# Inverter.net
KiCad netlist of a schematic drawn in Altium Designer
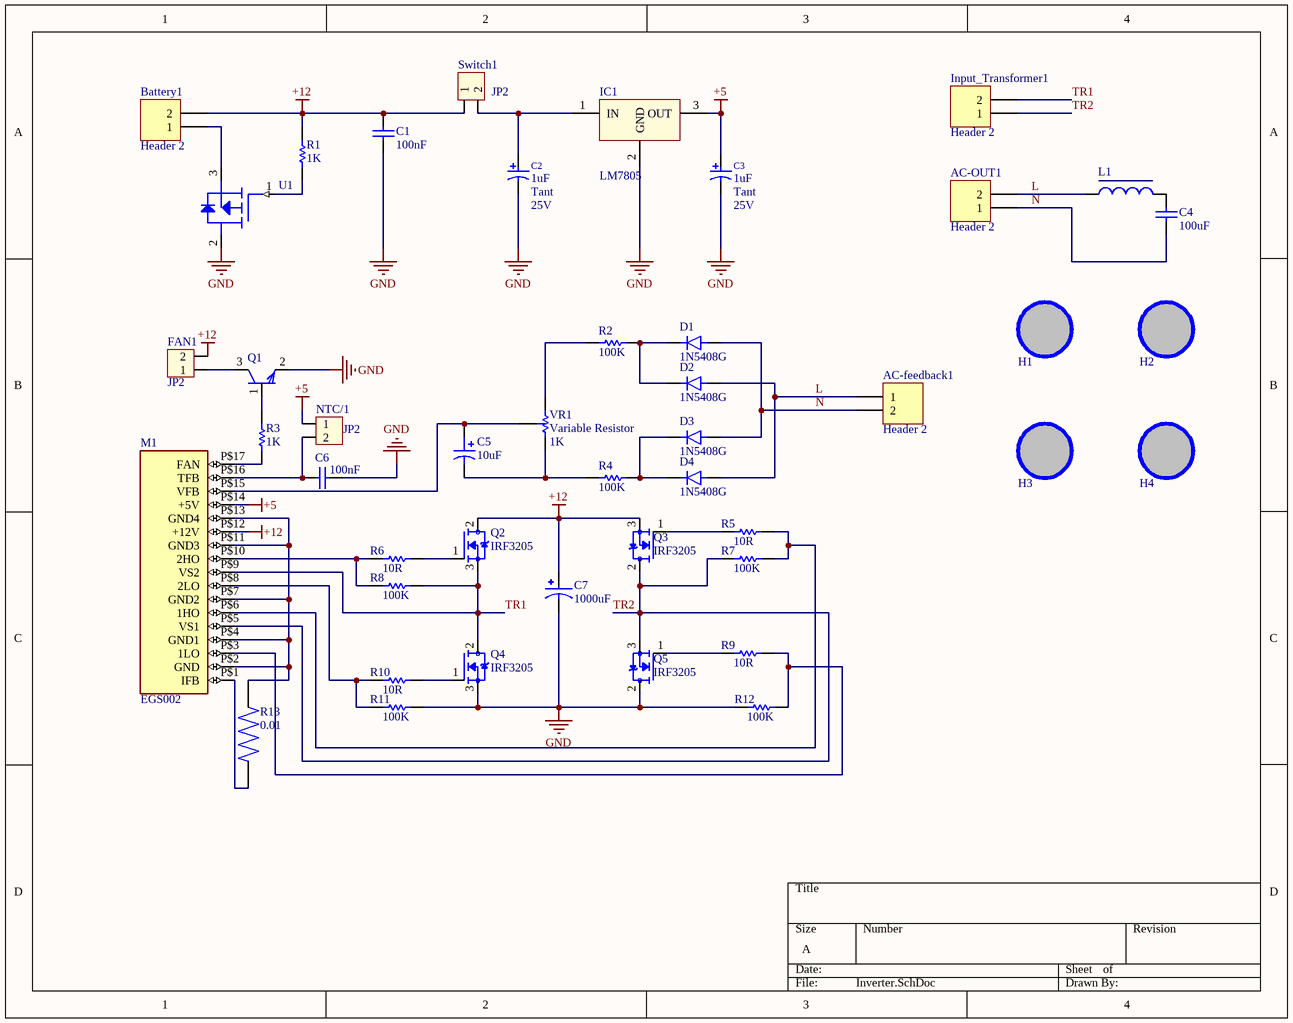
[diagram p0: Inverter.SchDoc]

(export (version "E")
  (design (tool "Eeschema 10.0.6"))
  (components
    (comp (ref "AC-feedback1")
      (value "Header 2")
      (footprint "PTBlock 2")
      (description "Header, 2-Pin")
      (fields (field (name "PUBLISHER") "Altium Limited"))
      (libsource (lib "") (part "Header 2_1"))
    )
    (comp (ref "AC-OUT1")
      (value "Header 2")
      (footprint "PTBlock 2")
      (description "Header, 2-Pin")
      (fields (field (name "PUBLISHER") "Altium Limited"))
      (libsource (lib "Kiet") (part "Header 2"))
    )
    (comp (ref "Battery1")
      (value "Header 2")
      (footprint "PTBlock 2")
      (description "Header, 2-Pin")
      (fields (field (name "PUBLISHER") "Altium Limited"))
      (libsource (lib "Kiet") (part "Header 2"))
    )
    (comp (ref "C1")
      (value "100nF")
      (footprint "Cap Non-Pol 3mm")
      (description "Non-polarized Capacitor")
      (fields (field (name "Comment") "Cap Non-pol") (field (name "PUBLISHER") "Altium Limited"))
      (libsource (lib "Kiet") (part "Cap Non-pol"))
    )
    (comp (ref "C2")
      (value "1uF")
      (footprint "RADIAL E")
      (description "Polarized Capacitor")
      (fields
        (field (name "MANUFACTURER") "FARNELL")
        (field (name "CAPACITOR TYPE") "Tant")
        (field (name "VOLT") "25V")
        (field (name "PUBLISHER") "Hoang Nguyen")
      )
      (libsource (lib "Kiet") (part "Cap_Pol"))
    )
    (comp (ref "C3")
      (value "1uF")
      (footprint "RADIAL E")
      (description "Polarized Capacitor")
      (fields
        (field (name "MANUFACTURER") "FARNELL")
        (field (name "CAPACITOR TYPE") "Tant")
        (field (name "VOLT") "25V")
        (field (name "PUBLISHER") "Hoang Nguyen")
      )
      (libsource (lib "Kiet") (part "Cap_Pol"))
    )
    (comp (ref "C4")
      (value "100uF")
      (footprint "Cap Non-Pol 5mm")
      (description "Non-polarized Capacitor")
      (fields (field (name "Comment") "Cap Non-pol") (field (name "PUBLISHER") "Altium Limited"))
      (libsource (lib "Kiet") (part "Cap Non-pol"))
    )
    (comp (ref "C5")
      (value "10uF")
      (footprint "RADIAL E")
      (description "Polarized Capacitor")
      (fields (field (name "Comment") "Cap Pol") (field (name "PUBLISHER") "Altium Limited"))
      (libsource (lib "Kiet") (part "Cap Pol"))
    )
    (comp (ref "C6")
      (value "100nF")
      (footprint "Cap Non-Pol 3mm")
      (description "Non-polarized Capacitor")
      (fields (field (name "Comment") "Cap Non-pol") (field (name "PUBLISHER") "Altium Limited"))
      (libsource (lib "Kiet") (part "Cap Non-pol"))
    )
    (comp (ref "C7")
      (value "1000uF")
      (footprint "CAPPRD750W80D1600H2500")
      (description "CAP ALUM 1000UF 20% 35V RADIAL")
      (fields (field (name "MF") "Panasonic Electronic Components") (field (name "MP") "EEU-TA1V102"))
      (libsource (lib "1000uF_ThroughHole") (part "EEUTA1V102"))
    )
    (comp (ref "D1")
      (value "1N5408G")
      (footprint "DIOAD1990W125L900D530")
      (description "DIODE GEN PURP 1KV 3A DO201AD ¦ ON Semiconductor 1N5408G")
      (fields (field (name "MF") "ON"))
      (libsource (lib "1N5408G") (part "1N5408G"))
    )
    (comp (ref "D2")
      (value "1N5408G")
      (footprint "DIOAD1990W125L900D530")
      (description "DIODE GEN PURP 1KV 3A DO201AD ¦ ON Semiconductor 1N5408G")
      (fields (field (name "MF") "ON"))
      (libsource (lib "1N5408G") (part "1N5408G"))
    )
    (comp (ref "D3")
      (value "1N5408G")
      (footprint "DIOAD1990W125L900D530")
      (description "DIODE GEN PURP 1KV 3A DO201AD ¦ ON Semiconductor 1N5408G")
      (fields (field (name "MF") "ON"))
      (libsource (lib "1N5408G") (part "1N5408G"))
    )
    (comp (ref "D4")
      (value "1N5408G")
      (footprint "DIOAD1990W125L900D530")
      (description "DIODE GEN PURP 1KV 3A DO201AD ¦ ON Semiconductor 1N5408G")
      (fields (field (name "MF") "ON"))
      (libsource (lib "1N5408G") (part "1N5408G"))
    )
    (comp (ref "FAN1")
      (value "JP2")
      (footprint "CON2")
      (description "Connector 2")
      (libsource (lib "") (part "Con2_2"))
    )
    (comp (ref "H1")
      (value "Hole")
      (footprint "LO KHOAN 3MM")
      (description "Hole 3mm")
      (libsource (lib "thuvienhoang") (part "Hole"))
    )
    (comp (ref "H2")
      (value "Hole")
      (footprint "LO KHOAN 3MM")
      (description "Hole 3mm")
      (libsource (lib "thuvienhoang") (part "Hole"))
    )
    (comp (ref "H3")
      (value "Hole")
      (footprint "LO KHOAN 3MM")
      (description "Hole 3mm")
      (libsource (lib "thuvienhoang") (part "Hole"))
    )
    (comp (ref "H4")
      (value "Hole")
      (footprint "LO KHOAN 3MM")
      (description "Hole 3mm")
      (libsource (lib "thuvienhoang") (part "Hole"))
    )
    (comp (ref "IC1")
      (value "LM7805")
      (footprint "QTO-220H3")
      (description "On ap +, from + 5 to + 24VDC")
      (libsource (lib "Kiet") (part "LM78xx_1"))
    )
    (comp (ref "Input_Transformer1")
      (value "Header 2")
      (footprint "PTBlock 2")
      (description "Header, 2-Pin")
      (fields (field (name "PUBLISHER") "Altium Limited"))
      (libsource (lib "Kiet") (part "Header 2"))
    )
    (comp (ref "L1")
      (value "~")
      (footprint "Cuon day ferrite")
      (description "Cuon Cam L")
      (fields (field (name "PUBLISHER") "Altium Limited"))
      (libsource (lib "Kiet") (part "Inductor Ferrite"))
    )
    (comp (ref "M1")
      (value "EGS002")
      (footprint "EGS002")
      (fields (field (name "MF") "EGmicro"))
      (libsource (lib "EGS002") (part "EGS002"))
    )
    (comp (ref "NTC/1")
      (value "JP2")
      (footprint "CON2")
      (description "Connector 2")
      (libsource (lib "Kiet") (part "Con2"))
    )
    (comp (ref "Q1")
      (value "C1815")
      (footprint "TO92-ECB-W")
      (description "Q2SC1815")
      (fields (field (name "PUBLISHER") "Hoang Nguyen"))
      (libsource (lib "Kiet") (part "C1815"))
    )
    (comp (ref "Q2")
      (value "IRF3205")
      (footprint "TO254P1067X483X3124-3P")
      (fields (field (name "MF") "Infineon Technologies") (field (name "MP") "IRF3205PBF"))
      (libsource (lib "IRF3205PBF") (part "IRF3205PBF"))
    )
    (comp (ref "Q3")
      (value "IRF3205")
      (footprint "TO254P1067X483X3124-3P")
      (fields (field (name "MF") "Infineon Technologies") (field (name "MP") "IRF3205PBF"))
      (libsource (lib "IRF3205PBF") (part "IRF3205PBF"))
    )
    (comp (ref "Q4")
      (value "IRF3205")
      (footprint "TO254P1067X483X3124-3P")
      (fields (field (name "MF") "Infineon Technologies") (field (name "MP") "IRF3205PBF"))
      (libsource (lib "IRF3205PBF") (part "IRF3205PBF"))
    )
    (comp (ref "Q5")
      (value "IRF3205")
      (footprint "TO254P1067X483X3124-3P")
      (fields (field (name "MF") "Infineon Technologies") (field (name "MP") "IRF3205PBF"))
      (libsource (lib "IRF3205PBF") (part "IRF3205PBF"))
    )
    (comp (ref "R1")
      (value "1K")
      (footprint "Res 10mm (1/2W)")
      (description "Resistor")
      (fields (field (name "Comment") "RESISTOR") (field (name "PUBLISHER") "Altium Limited"))
      (libsource (lib "Kiet") (part "RESISTOR"))
    )
    (comp (ref "R2")
      (value "100K")
      (footprint "Res 10mm (1/2W)")
      (description "Resistor")
      (fields (field (name "Comment") "RESISTOR") (field (name "PUBLISHER") "Altium Limited"))
      (libsource (lib "Kiet") (part "RESISTOR"))
    )
    (comp (ref "R3")
      (value "1K")
      (footprint "R-0805")
      (description "Resistor")
      (fields (field (name "Comment") "RESISTOR") (field (name "PUBLISHER") "Altium Limited"))
      (libsource (lib "Kiet") (part "RESISTOR"))
    )
    (comp (ref "R4")
      (value "100K")
      (footprint "Res 10mm (1/2W)")
      (description "Resistor")
      (fields (field (name "Comment") "RESISTOR") (field (name "PUBLISHER") "Altium Limited"))
      (libsource (lib "Kiet") (part "RESISTOR"))
    )
    (comp (ref "R5")
      (value "10R")
      (footprint "Res 10mm (1/2W)")
      (description "Resistor")
      (fields (field (name "Comment") "RESISTOR") (field (name "PUBLISHER") "Altium Limited"))
      (libsource (lib "Kiet") (part "RESISTOR"))
    )
    (comp (ref "R6")
      (value "10R")
      (footprint "Res 10mm (1/2W)")
      (description "Resistor")
      (fields (field (name "Comment") "RESISTOR") (field (name "PUBLISHER") "Altium Limited"))
      (libsource (lib "Kiet") (part "RESISTOR"))
    )
    (comp (ref "R7")
      (value "100K")
      (footprint "Res 10mm (1/2W)")
      (description "Resistor")
      (fields (field (name "Comment") "RESISTOR") (field (name "PUBLISHER") "Altium Limited"))
      (libsource (lib "Kiet") (part "RESISTOR"))
    )
    (comp (ref "R8")
      (value "100K")
      (footprint "Res 10mm (1/2W)")
      (description "Resistor")
      (fields (field (name "Comment") "RESISTOR") (field (name "PUBLISHER") "Altium Limited"))
      (libsource (lib "Kiet") (part "RESISTOR"))
    )
    (comp (ref "R9")
      (value "10R")
      (footprint "Res 10mm (1/2W)")
      (description "Resistor")
      (fields (field (name "Comment") "RESISTOR") (field (name "PUBLISHER") "Altium Limited"))
      (libsource (lib "Kiet") (part "RESISTOR"))
    )
    (comp (ref "R10")
      (value "10R")
      (footprint "Res 10mm (1/2W)")
      (description "Resistor")
      (fields (field (name "Comment") "RESISTOR") (field (name "PUBLISHER") "Altium Limited"))
      (libsource (lib "Kiet") (part "RESISTOR"))
    )
    (comp (ref "R11")
      (value "100K")
      (footprint "Res 10mm (1/2W)")
      (description "Resistor")
      (fields (field (name "Comment") "RESISTOR") (field (name "PUBLISHER") "Altium Limited"))
      (libsource (lib "Kiet") (part "RESISTOR"))
    )
    (comp (ref "R12")
      (value "100K")
      (footprint "Res 10mm (1/2W)")
      (description "Resistor")
      (fields (field (name "Comment") "RESISTOR") (field (name "PUBLISHER") "Altium Limited"))
      (libsource (lib "Kiet") (part "RESISTOR"))
    )
    (comp (ref "R13")
      (value "0.01")
      (footprint "RESC6432X75N")
      (description "CRS Series Anti-surge Resistor 2512 Case 1Ohms 2W +/-200ppm/degC ¦ Bourns CRS2512-FW-1R00ELF")
      (fields (field (name "MF") "Bourns") (field (name "MP") "CRS2512-FW-1R00ELF"))
      (libsource (lib "CRS2512-FW-1R00ELF") (part "CRS2512-FW-1R00ELF"))
    )
    (comp (ref "Switch1")
      (value "JP2")
      (footprint "CON2")
      (description "Connector 2")
      (libsource (lib "") (part "Con2_1"))
    )
    (comp (ref "U1")
      (value "IRF9540")
      (footprint "TO-263")
      (description "IRF9540 - P-CHANNEL POWER MOSFETS")
      (fields (field (name "PUBLISHER") "Hoang Nguyen"))
      (libsource (lib "Kiet") (part "IRF9540"))
    )
    (comp (ref "VR1")
      (value "Variable Resistor")
      (footprint "VRes-S")
      (fields (field (name "ALTIUM_VALUE") "1K") (field (name "PUBLISHER") "Altium Limited"))
      (libsource (lib "Kiet") (part "Variable Resistor"))
    )
  )
  (nets
    (net (code "1") (name "+5") (class "Default")
      (node (ref "C3") (pin "1") (pinfunction "1_1") (pintype "passive"))
      (node (ref "IC1") (pin "3") (pinfunction "OUT_3") (pintype "passive"))
      (node (ref "M1") (pin "P$14") (pinfunction "+5V_P$14") (pintype "bidirectional"))
      (node (ref "NTC/1") (pin "1") (pinfunction "1_1") (pintype "passive"))
    )
    (net (code "2") (name "+12") (class "Default")
      (node (ref "Battery1") (pin "2") (pinfunction "2_2") (pintype "passive"))
      (node (ref "C1") (pin "2") (pinfunction "2_2") (pintype "passive"))
      (node (ref "C7") (pin "P") (pinfunction "P_P") (pintype "passive"))
      (node (ref "FAN1") (pin "2") (pinfunction "2_2") (pintype "passive"))
      (node (ref "M1") (pin "P$12") (pinfunction "+12V_P$12") (pintype "bidirectional"))
      (node (ref "Q2") (pin "2") (pinfunction "D_2") (pintype "passive"))
      (node (ref "Q3") (pin "3") (pinfunction "S_3") (pintype "passive"))
      (node (ref "R1") (pin "2") (pinfunction "2_2") (pintype "passive"))
      (node (ref "Switch1") (pin "1") (pinfunction "1_1") (pintype "passive"))
    )
    (net (code "3") (name "/L") (class "Default")
      (node (ref "AC-OUT1") (pin "2") (pinfunction "2_2") (pintype "passive"))
      (node (ref "AC-feedback1") (pin "1") (pinfunction "1_1") (pintype "passive"))
      (node (ref "D2") (pin "A") (pinfunction "A_A") (pintype "passive"))
      (node (ref "D4") (pin "A") (pinfunction "A_A") (pintype "passive"))
      (node (ref "L1") (pin "1") (pinfunction "1_1") (pintype "passive"))
    )
    (net (code "4") (name "/N") (class "Default")
      (node (ref "AC-OUT1") (pin "1") (pinfunction "1_1") (pintype "passive"))
      (node (ref "AC-feedback1") (pin "2") (pinfunction "2_2") (pintype "passive"))
      (node (ref "C4") (pin "1") (pinfunction "1_1") (pintype "passive"))
      (node (ref "D1") (pin "A") (pinfunction "A_A") (pintype "passive"))
      (node (ref "D3") (pin "A") (pinfunction "A_A") (pintype "passive"))
    )
    (net (code "5") (name "/TR1") (class "Default")
      (node (ref "Input_Transformer1") (pin "2") (pinfunction "2_2") (pintype "passive"))
      (node (ref "M1") (pin "P$9") (pinfunction "VS2_P$9") (pintype "bidirectional"))
      (node (ref "Q2") (pin "3") (pinfunction "S_3") (pintype "passive"))
      (node (ref "Q4") (pin "2") (pinfunction "D_2") (pintype "passive"))
      (node (ref "R8") (pin "1") (pinfunction "1_1") (pintype "passive"))
    )
    (net (code "6") (name "/TR2") (class "Default")
      (node (ref "Input_Transformer1") (pin "1") (pinfunction "1_1") (pintype "passive"))
      (node (ref "M1") (pin "P$5") (pinfunction "VS1_P$5") (pintype "bidirectional"))
      (node (ref "Q3") (pin "2") (pinfunction "D_2") (pintype "passive"))
      (node (ref "Q5") (pin "3") (pinfunction "S_3") (pintype "passive"))
      (node (ref "R7") (pin "2") (pinfunction "2_2") (pintype "passive"))
    )
    (net (code "7") (name "GND") (class "Default")
      (node (ref "C1") (pin "1") (pinfunction "1_1") (pintype "passive"))
      (node (ref "C2") (pin "2") (pinfunction "2_2") (pintype "passive"))
      (node (ref "C3") (pin "2") (pinfunction "2_2") (pintype "passive"))
      (node (ref "C6") (pin "1") (pinfunction "1_1") (pintype "passive"))
      (node (ref "C7") (pin "N") (pinfunction "N_N") (pintype "passive"))
      (node (ref "IC1") (pin "2") (pinfunction "GND_2") (pintype "passive"))
      (node (ref "Q1") (pin "2") (pinfunction "E_2") (pintype "passive"))
      (node (ref "Q4") (pin "3") (pinfunction "S_3") (pintype "passive"))
      (node (ref "Q5") (pin "2") (pinfunction "D_2") (pintype "passive"))
      (node (ref "R11") (pin "1") (pinfunction "1_1") (pintype "passive"))
      (node (ref "R12") (pin "2") (pinfunction "2_2") (pintype "passive"))
      (node (ref "U1") (pin "2") (pinfunction "D_2") (pintype "passive"))
    )
    (net (code "8") (name "Net-(C4-Pad2)") (class "Default")
      (node (ref "C4") (pin "2") (pinfunction "2_2") (pintype "passive"))
      (node (ref "L1") (pin "2") (pinfunction "2_2") (pintype "passive"))
    )
    (net (code "9") (name "Net-(C5-Pad2)") (class "Default")
      (node (ref "C5") (pin "2") (pinfunction "2_2") (pintype "passive"))
      (node (ref "R4") (pin "2") (pinfunction "2_2") (pintype "passive"))
      (node (ref "VR1") (pin "3") (pinfunction "3_3") (pintype "passive"))
    )
    (net (code "10") (name "Net-(D1-K)") (class "Default")
      (node (ref "D1") (pin "C") (pinfunction "K_C") (pintype "passive"))
      (node (ref "D2") (pin "C") (pinfunction "K_C") (pintype "passive"))
      (node (ref "R2") (pin "1") (pinfunction "1_1") (pintype "passive"))
    )
    (net (code "11") (name "Net-(D3-K)") (class "Default")
      (node (ref "D3") (pin "C") (pinfunction "K_C") (pintype "passive"))
      (node (ref "D4") (pin "C") (pinfunction "K_C") (pintype "passive"))
      (node (ref "R4") (pin "1") (pinfunction "1_1") (pintype "passive"))
    )
    (net (code "12") (name "Net-(IC1-IN)") (class "Default")
      (node (ref "C2") (pin "1") (pinfunction "1_1") (pintype "passive"))
      (node (ref "IC1") (pin "1") (pinfunction "IN_1") (pintype "passive"))
      (node (ref "Switch1") (pin "2") (pinfunction "2_2") (pintype "passive"))
    )
    (net (code "13") (name "Net-(M1-1HO)") (class "Default")
      (node (ref "M1") (pin "P$6") (pinfunction "1HO_P$6") (pintype "bidirectional"))
      (node (ref "R5") (pin "1") (pinfunction "1_1") (pintype "passive"))
      (node (ref "R7") (pin "1") (pinfunction "1_1") (pintype "passive"))
    )
    (net (code "14") (name "Net-(M1-1LO)") (class "Default")
      (node (ref "M1") (pin "P$3") (pinfunction "1LO_P$3") (pintype "bidirectional"))
      (node (ref "R12") (pin "1") (pinfunction "1_1") (pintype "passive"))
      (node (ref "R9") (pin "1") (pinfunction "1_1") (pintype "passive"))
    )
    (net (code "15") (name "Net-(M1-2HO)") (class "Default")
      (node (ref "M1") (pin "P$10") (pinfunction "2HO_P$10") (pintype "bidirectional"))
      (node (ref "R6") (pin "2") (pinfunction "2_2") (pintype "passive"))
      (node (ref "R8") (pin "2") (pinfunction "2_2") (pintype "passive"))
    )
    (net (code "16") (name "Net-(M1-2LO)") (class "Default")
      (node (ref "M1") (pin "P$8") (pinfunction "2LO_P$8") (pintype "bidirectional"))
      (node (ref "R10") (pin "2") (pinfunction "2_2") (pintype "passive"))
      (node (ref "R11") (pin "2") (pinfunction "2_2") (pintype "passive"))
    )
    (net (code "17") (name "Net-(M1-FAN)") (class "Default")
      (node (ref "M1") (pin "P$17") (pinfunction "FAN_P$17") (pintype "bidirectional"))
      (node (ref "R3") (pin "1") (pinfunction "1_1") (pintype "passive"))
    )
    (net (code "18") (name "Net-(M1-GND)") (class "Default")
      (node (ref "M1") (pin "P$11") (pinfunction "GND3_P$11") (pintype "bidirectional"))
      (node (ref "M1") (pin "P$13") (pinfunction "GND4_P$13") (pintype "bidirectional"))
      (node (ref "M1") (pin "P$2") (pinfunction "GND_P$2") (pintype "bidirectional"))
      (node (ref "M1") (pin "P$4") (pinfunction "GND1_P$4") (pintype "bidirectional"))
      (node (ref "M1") (pin "P$7") (pinfunction "GND2_P$7") (pintype "bidirectional"))
      (node (ref "R13") (pin "2") (pinfunction "2_2") (pintype "passive"))
    )
    (net (code "19") (name "Net-(M1-IFB)") (class "Default")
      (node (ref "M1") (pin "P$1") (pinfunction "IFB_P$1") (pintype "bidirectional"))
      (node (ref "R13") (pin "1") (pinfunction "1_1") (pintype "passive"))
    )
    (net (code "20") (name "Net-(M1-TFB)") (class "Default")
      (node (ref "C6") (pin "2") (pinfunction "2_2") (pintype "passive"))
      (node (ref "M1") (pin "P$16") (pinfunction "TFB_P$16") (pintype "bidirectional"))
      (node (ref "NTC/1") (pin "2") (pinfunction "2_2") (pintype "passive"))
    )
    (net (code "21") (name "Net-(M1-VFB)") (class "Default")
      (node (ref "C5") (pin "1") (pinfunction "1_1") (pintype "passive"))
      (node (ref "M1") (pin "P$15") (pinfunction "VFB_P$15") (pintype "bidirectional"))
      (node (ref "VR1") (pin "2") (pinfunction "2_2") (pintype "passive"))
    )
    (net (code "22") (name "Net-(Q1-B)") (class "Default")
      (node (ref "Q1") (pin "1") (pinfunction "B_1") (pintype "passive"))
      (node (ref "R3") (pin "2") (pinfunction "2_2") (pintype "passive"))
    )
    (net (code "23") (name "Net-(Q1-C)") (class "Default")
      (node (ref "FAN1") (pin "1") (pinfunction "1_1") (pintype "passive"))
      (node (ref "Q1") (pin "3") (pinfunction "C_3") (pintype "passive"))
    )
    (net (code "24") (name "Net-(Q2-G)") (class "Default")
      (node (ref "Q2") (pin "1") (pinfunction "G_1") (pintype "passive"))
      (node (ref "R6") (pin "1") (pinfunction "1_1") (pintype "passive"))
    )
    (net (code "25") (name "Net-(Q3-G)") (class "Default")
      (node (ref "Q3") (pin "1") (pinfunction "G_1") (pintype "passive"))
      (node (ref "R5") (pin "2") (pinfunction "2_2") (pintype "passive"))
    )
    (net (code "26") (name "Net-(Q4-G)") (class "Default")
      (node (ref "Q4") (pin "1") (pinfunction "G_1") (pintype "passive"))
      (node (ref "R10") (pin "1") (pinfunction "1_1") (pintype "passive"))
    )
    (net (code "27") (name "Net-(Q5-G)") (class "Default")
      (node (ref "Q5") (pin "1") (pinfunction "G_1") (pintype "passive"))
      (node (ref "R9") (pin "2") (pinfunction "2_2") (pintype "passive"))
    )
    (net (code "28") (name "Net-(R2-Pad2)") (class "Default")
      (node (ref "R2") (pin "2") (pinfunction "2_2") (pintype "passive"))
      (node (ref "VR1") (pin "1") (pinfunction "1_1") (pintype "passive"))
    )
    (net (code "29") (name "Net-(U1-G)") (class "Default")
      (node (ref "R1") (pin "1") (pinfunction "1_1") (pintype "passive"))
      (node (ref "U1") (pin "1") (pinfunction "G_1") (pintype "input"))
    )
    (net (code "30") (name "Net-(U1-S)") (class "Default")
      (node (ref "Battery1") (pin "1") (pinfunction "1_1") (pintype "passive"))
      (node (ref "U1") (pin "3") (pinfunction "S_3") (pintype "passive"))
    )
    (net (code "31") (name "unconnected-(H1-Pad1)") (class "Default")
      (node (ref "H1") (pin "1") (pinfunction "1_1") (pintype "passive"))
    )
    (net (code "32") (name "unconnected-(H2-Pad1)") (class "Default")
      (node (ref "H2") (pin "1") (pinfunction "1_1") (pintype "passive"))
    )
    (net (code "33") (name "unconnected-(H3-Pad1)") (class "Default")
      (node (ref "H3") (pin "1") (pinfunction "1_1") (pintype "passive"))
    )
    (net (code "34") (name "unconnected-(H4-Pad1)") (class "Default")
      (node (ref "H4") (pin "1") (pinfunction "1_1") (pintype "passive"))
    )
  )
)
